# 1_power.net
KiCad netlist of a schematic drawn in Altium Designer
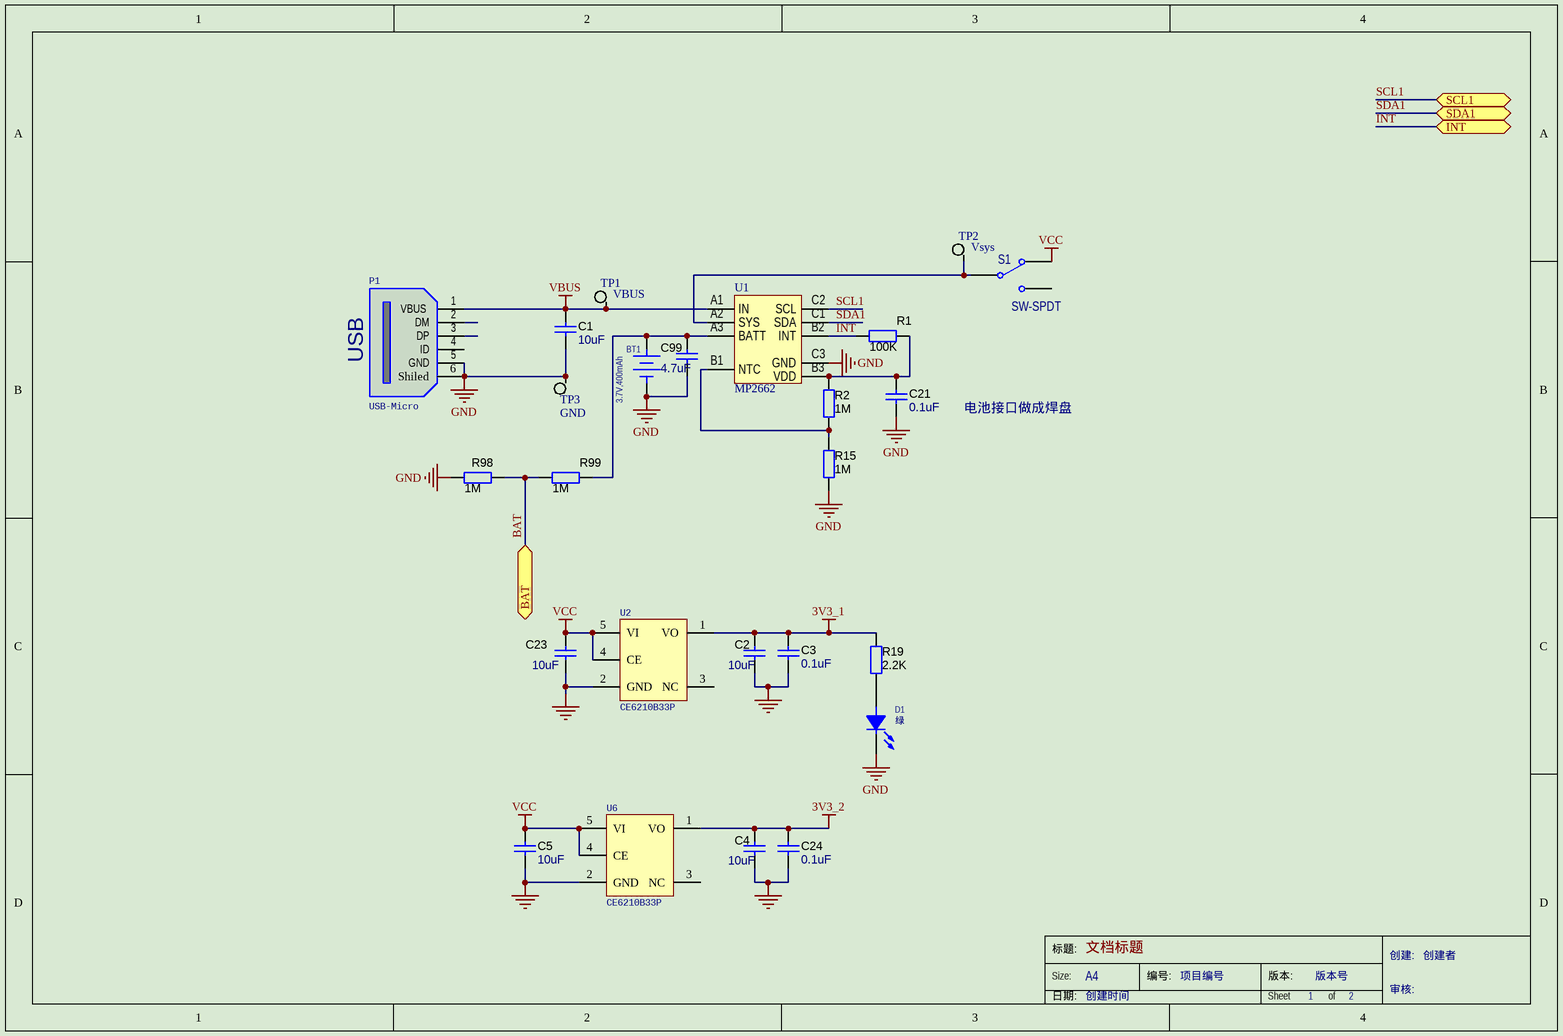
[diagram p0: 1.power.SchDoc]

(export (version "E")
  (design (tool "Eeschema 10.0.6"))
  (components
    (comp (ref "BT1")
      (value "3.7V,400mAh")
      (footprint "2P/1.0MM立式贴片座子")
      (description "4.2V Li-lon")
      (fields (field (name "MANUFACTURER") "?"))
      (libsource (lib "03.常用器件") (part "Battery"))
    )
    (comp (ref "C1")
      (value "10uF")
      (footprint "0603")
      (description "CAP, CERM, 0.01uF, 100V, +/-5%, X7R, 0603")
      (fields (field (name "PARTNUMBER") "06031C103JAT2A") (field (name "MANUFACTURER") "AVX"))
      (libsource (lib "03.常用器件") (part "CAP1_npol"))
    )
    (comp (ref "C2")
      (value "10uF")
      (footprint "0603")
      (description "CAP, CERM, 0.01uF, 100V, +/-5%, X7R, 0603")
      (fields (field (name "PARTNUMBER") "06031C103JAT2A") (field (name "MANUFACTURER") "AVX"))
      (libsource (lib "03.常用器件") (part "CAP1_npol"))
    )
    (comp (ref "C3")
      (value "0.1uF")
      (footprint "0402")
      (description "CAP, CERM, 0.01uF, 100V, +/-5%, X7R, 0603")
      (fields (field (name "PARTNUMBER") "06031C103JAT2A") (field (name "MANUFACTURER") "AVX"))
      (libsource (lib "03.常用器件") (part "CAP1_npol"))
    )
    (comp (ref "C4")
      (value "10uF")
      (footprint "0603")
      (description "CAP, CERM, 0.01uF, 100V, +/-5%, X7R, 0603")
      (fields (field (name "PARTNUMBER") "06031C103JAT2A") (field (name "MANUFACTURER") "AVX"))
      (libsource (lib "03.常用器件") (part "CAP1_npol"))
    )
    (comp (ref "C5")
      (value "10uF")
      (footprint "0603")
      (description "CAP, CERM, 0.01uF, 100V, +/-5%, X7R, 0603")
      (fields (field (name "PARTNUMBER") "06031C103JAT2A") (field (name "MANUFACTURER") "AVX"))
      (libsource (lib "03.常用器件") (part "CAP1_npol"))
    )
    (comp (ref "C21")
      (value "0.1uF")
      (footprint "0603")
      (description "CAP, CERM, 0.01uF, 100V, +/-5%, X7R, 0603")
      (fields (field (name "PARTNUMBER") "06031C103JAT2A") (field (name "MANUFACTURER") "AVX"))
      (libsource (lib "03.常用器件") (part "CAP1_npol"))
    )
    (comp (ref "C23")
      (value "10uF")
      (footprint "0603")
      (description "CAP, CERM, 0.01uF, 100V, +/-5%, X7R, 0603")
      (fields (field (name "PARTNUMBER") "06031C103JAT2A") (field (name "MANUFACTURER") "AVX"))
      (libsource (lib "03.常用器件") (part "CAP1_npol"))
    )
    (comp (ref "C24")
      (value "0.1uF")
      (footprint "0402")
      (description "CAP, CERM, 0.01uF, 100V, +/-5%, X7R, 0603")
      (fields (field (name "PARTNUMBER") "06031C103JAT2A") (field (name "MANUFACTURER") "AVX"))
      (libsource (lib "03.常用器件") (part "CAP1_npol"))
    )
    (comp (ref "C99")
      (value "4.7uF")
      (footprint "0603")
      (description "CAP, CERM, 0.01uF, 100V, +/-5%, X7R, 0603")
      (fields (field (name "PARTNUMBER") "06031C103JAT2A") (field (name "MANUFACTURER") "AVX"))
      (libsource (lib "03.常用器件") (part "CAP1_npol"))
    )
    (comp (ref "D1")
      (value "绿")
      (footprint "0603LED")
      (fields (field (name "MANUFACTURER") "?"))
      (libsource (lib "03.常用器件") (part "LED1"))
    )
    (comp (ref "P1")
      (value "USB-Micro")
      (footprint "MICRO_USB2")
      (description "USB Connector")
      (libsource (lib "misc") (part "USB-Micro"))
    )
    (comp (ref "R1")
      (value "100K")
      (footprint "0402")
      (description "RES, 1.0k ohm, 5%, 0.1W, 0603")
      (fields
        (field (name "PARTNUMBER") "RC0603JR-071KL")
        (field (name "MANUFACTURER") "Yageo America")
        (field (name "PUBLISHER") "Texas Instruments")
      )
      (libsource (lib "03.常用器件") (part "RES1"))
    )
    (comp (ref "R2")
      (value "1M")
      (footprint "0402")
      (description "RES, 1.0k ohm, 5%, 0.1W, 0603")
      (fields
        (field (name "PARTNUMBER") "RC0603JR-071KL")
        (field (name "MANUFACTURER") "Yageo America")
        (field (name "PUBLISHER") "Texas Instruments")
      )
      (libsource (lib "") (part "RES1_1"))
    )
    (comp (ref "R15")
      (value "1M")
      (footprint "0402")
      (description "RES, 1.0k ohm, 5%, 0.1W, 0603")
      (fields
        (field (name "PARTNUMBER") "RC0603JR-071KL")
        (field (name "MANUFACTURER") "Yageo America")
        (field (name "PUBLISHER") "Texas Instruments")
      )
      (libsource (lib "") (part "RES1_1"))
    )
    (comp (ref "R19")
      (value "2.2K")
      (footprint "0402")
      (description "RES, 1.0k ohm, 5%, 0.1W, 0603")
      (fields
        (field (name "PARTNUMBER") "RC0603JR-071KL")
        (field (name "MANUFACTURER") "Yageo America")
        (field (name "PUBLISHER") "Texas Instruments")
      )
      (libsource (lib "") (part "RES1_1"))
    )
    (comp (ref "R98")
      (value "1M")
      (footprint "0402")
      (description "RES, 1.0k ohm, 5%, 0.1W, 0603")
      (fields
        (field (name "PARTNUMBER") "RC0603JR-071KL")
        (field (name "MANUFACTURER") "Yageo America")
        (field (name "PUBLISHER") "Texas Instruments")
      )
      (libsource (lib "03.常用器件") (part "RES1"))
    )
    (comp (ref "R99")
      (value "1M")
      (footprint "0402")
      (description "RES, 1.0k ohm, 5%, 0.1W, 0603")
      (fields
        (field (name "PARTNUMBER") "RC0603JR-071KL")
        (field (name "MANUFACTURER") "Yageo America")
        (field (name "PUBLISHER") "Texas Instruments")
      )
      (libsource (lib "03.常用器件") (part "RES1"))
    )
    (comp (ref "S1")
      (value "SW-SPDT")
      (footprint "SW2")
      (description "SPDT Subminiature Toggle Switch, Right Angle Mounting, Vertical Actuation")
      (fields (field (name "PUBLISHER") "Altium Limited"))
      (libsource (lib "Miscellaneous Devices") (part "SW-SPDT"))
    )
    (comp (ref "TP1")
      (value "VBUS")
      (footprint "测试点")
      (description "Test Point")
      (libsource (lib "my_Schlib") (part "TP"))
    )
    (comp (ref "TP2")
      (value "Vsys")
      (footprint "测试点")
      (description "Test Point")
      (libsource (lib "my_Schlib") (part "TP"))
    )
    (comp (ref "TP3")
      (value "GND")
      (footprint "测试点")
      (description "Test Point")
      (libsource (lib "my_Schlib") (part "TP"))
    )
    (comp (ref "U1") (value "MP2662") (footprint "WLCSP-9") (libsource (lib "Schlib1") (part "MP2662")))
    (comp (ref "U2")
      (value "CE6210B33P")
      (footprint "SOT89-5")
      (libsource (lib "altium-import") (part "root_0_AP2112K_"))
    )
    (comp (ref "U6")
      (value "CE6210B33P")
      (footprint "SOT89-5")
      (libsource (lib "altium-import") (part "root_0_AP2112K_"))
    )
  )
  (nets
    (net (code "1") (name "/BAT") (class "Default")
      (node (ref "R98") (pin "2") (pinfunction "2_2") (pintype "passive"))
      (node (ref "R99") (pin "1") (pinfunction "1_1") (pintype "passive"))
    )
    (net (code "2") (name "/INT") (class "Default")
      (node (ref "R1") (pin "1") (pinfunction "1_1") (pintype "passive"))
      (node (ref "U1") (pin "B2") (pinfunction "INT_B2") (pintype "passive"))
    )
    (net (code "3") (name "/SCL1") (class "Default")
      (node (ref "U1") (pin "C2") (pinfunction "SCL_C2") (pintype "passive"))
    )
    (net (code "4") (name "/SDA1") (class "Default")
      (node (ref "U1") (pin "C1") (pinfunction "SDA_C1") (pintype "passive"))
    )
    (net (code "5") (name "3V3_1") (class "Default")
      (node (ref "C2") (pin "1") (pinfunction "1_1") (pintype "passive"))
      (node (ref "C3") (pin "2") (pinfunction "2_2") (pintype "passive"))
      (node (ref "R19") (pin "1") (pinfunction "1_1") (pintype "passive"))
      (node (ref "U2") (pin "1") (pinfunction "VO_1") (pintype "passive"))
    )
    (net (code "6") (name "3V3_2") (class "Default")
      (node (ref "C24") (pin "2") (pinfunction "2_2") (pintype "passive"))
      (node (ref "C4") (pin "1") (pinfunction "1_1") (pintype "passive"))
      (node (ref "U6") (pin "1") (pinfunction "VO_1") (pintype "passive"))
    )
    (net (code "7") (name "GND") (class "Default")
      (node (ref "BT1") (pin "2") (pinfunction "-_2") (pintype "passive"))
      (node (ref "C1") (pin "2") (pinfunction "2_2") (pintype "passive"))
      (node (ref "C2") (pin "2") (pinfunction "2_2") (pintype "passive"))
      (node (ref "C21") (pin "2") (pinfunction "2_2") (pintype "passive"))
      (node (ref "C23") (pin "2") (pinfunction "2_2") (pintype "passive"))
      (node (ref "C24") (pin "1") (pinfunction "1_1") (pintype "passive"))
      (node (ref "C3") (pin "1") (pinfunction "1_1") (pintype "passive"))
      (node (ref "C4") (pin "2") (pinfunction "2_2") (pintype "passive"))
      (node (ref "C5") (pin "2") (pinfunction "2_2") (pintype "passive"))
      (node (ref "C99") (pin "2") (pinfunction "2_2") (pintype "passive"))
      (node (ref "D1") (pin "C") (pinfunction "CATHODE_C") (pintype "passive"))
      (node (ref "P1") (pin "5") (pinfunction "GND_5") (pintype "passive"))
      (node (ref "P1") (pin "6") (pinfunction "Shiled_6") (pintype "passive"))
      (node (ref "R15") (pin "2") (pinfunction "2_2") (pintype "passive"))
      (node (ref "R98") (pin "1") (pinfunction "1_1") (pintype "passive"))
      (node (ref "TP3") (pin "1") (pinfunction "1_1") (pintype "passive"))
      (node (ref "U1") (pin "C3") (pinfunction "GND_C3") (pintype "passive"))
      (node (ref "U2") (pin "2") (pinfunction "GND_2") (pintype "passive"))
      (node (ref "U6") (pin "2") (pinfunction "GND_2") (pintype "passive"))
    )
    (net (code "8") (name "Net-(BT1-+)") (class "Default")
      (node (ref "BT1") (pin "1") (pinfunction "+_1") (pintype "passive"))
      (node (ref "C99") (pin "1") (pinfunction "1_1") (pintype "passive"))
      (node (ref "R99") (pin "2") (pinfunction "2_2") (pintype "passive"))
      (node (ref "U1") (pin "A3") (pinfunction "BATT_A3") (pintype "passive"))
    )
    (net (code "9") (name "Net-(D1-ANODE)") (class "Default")
      (node (ref "D1") (pin "A") (pinfunction "ANODE_A") (pintype "passive"))
      (node (ref "R19") (pin "2") (pinfunction "2_2") (pintype "passive"))
    )
    (net (code "10") (name "Net-(U1-NTC)") (class "Default")
      (node (ref "R15") (pin "1") (pinfunction "1_1") (pintype "passive"))
      (node (ref "R2") (pin "2") (pinfunction "2_2") (pintype "passive"))
      (node (ref "U1") (pin "B1") (pinfunction "NTC_B1") (pintype "power_in"))
    )
    (net (code "11") (name "Net-(U1-SYS)") (class "Default")
      (node (ref "S1") (pin "2") (pinfunction "2_2") (pintype "passive"))
      (node (ref "TP2") (pin "1") (pinfunction "1_1") (pintype "passive"))
      (node (ref "U1") (pin "A2") (pinfunction "SYS_A2") (pintype "passive"))
    )
    (net (code "12") (name "Net-(U1-VDD)") (class "Default")
      (node (ref "C21") (pin "1") (pinfunction "1_1") (pintype "passive"))
      (node (ref "R1") (pin "2") (pinfunction "2_2") (pintype "passive"))
      (node (ref "R2") (pin "1") (pinfunction "1_1") (pintype "passive"))
      (node (ref "U1") (pin "B3") (pinfunction "VDD_B3") (pintype "passive"))
    )
    (net (code "13") (name "VBUS") (class "Default")
      (node (ref "C1") (pin "1") (pinfunction "1_1") (pintype "passive"))
      (node (ref "P1") (pin "1") (pinfunction "VBUS_1") (pintype "passive"))
      (node (ref "TP1") (pin "1") (pinfunction "1_1") (pintype "passive"))
      (node (ref "U1") (pin "A1") (pinfunction "IN_A1") (pintype "passive"))
    )
    (net (code "14") (name "VCC") (class "Default")
      (node (ref "C23") (pin "1") (pinfunction "1_1") (pintype "passive"))
      (node (ref "C5") (pin "1") (pinfunction "1_1") (pintype "passive"))
      (node (ref "S1") (pin "3") (pinfunction "3_3") (pintype "passive"))
      (node (ref "U2") (pin "4") (pinfunction "CE_4") (pintype "passive"))
      (node (ref "U2") (pin "5") (pinfunction "VI_5") (pintype "passive"))
      (node (ref "U6") (pin "4") (pinfunction "CE_4") (pintype "passive"))
      (node (ref "U6") (pin "5") (pinfunction "VI_5") (pintype "passive"))
    )
    (net (code "15") (name "unconnected-(P1-DM-Pad2)") (class "Default")
      (node (ref "P1") (pin "2") (pinfunction "DM_2") (pintype "passive"))
    )
    (net (code "16") (name "unconnected-(P1-DP-Pad3)") (class "Default")
      (node (ref "P1") (pin "3") (pinfunction "DP_3") (pintype "passive"))
    )
    (net (code "17") (name "unconnected-(P1-ID-Pad4)") (class "Default")
      (node (ref "P1") (pin "4") (pinfunction "ID_4") (pintype "passive"))
    )
    (net (code "18") (name "unconnected-(S1-Pad1)") (class "Default")
      (node (ref "S1") (pin "1") (pinfunction "1_1") (pintype "passive"))
    )
    (net (code "19") (name "unconnected-(U2-NC-Pad3)") (class "Default")
      (node (ref "U2") (pin "3") (pinfunction "NC_3") (pintype "passive"))
    )
    (net (code "20") (name "unconnected-(U6-NC-Pad3)") (class "Default")
      (node (ref "U6") (pin "3") (pinfunction "NC_3") (pintype "passive"))
    )
  )
)
